# e1-xover.net
KiCad netlist of a schematic drawn in EAGLE
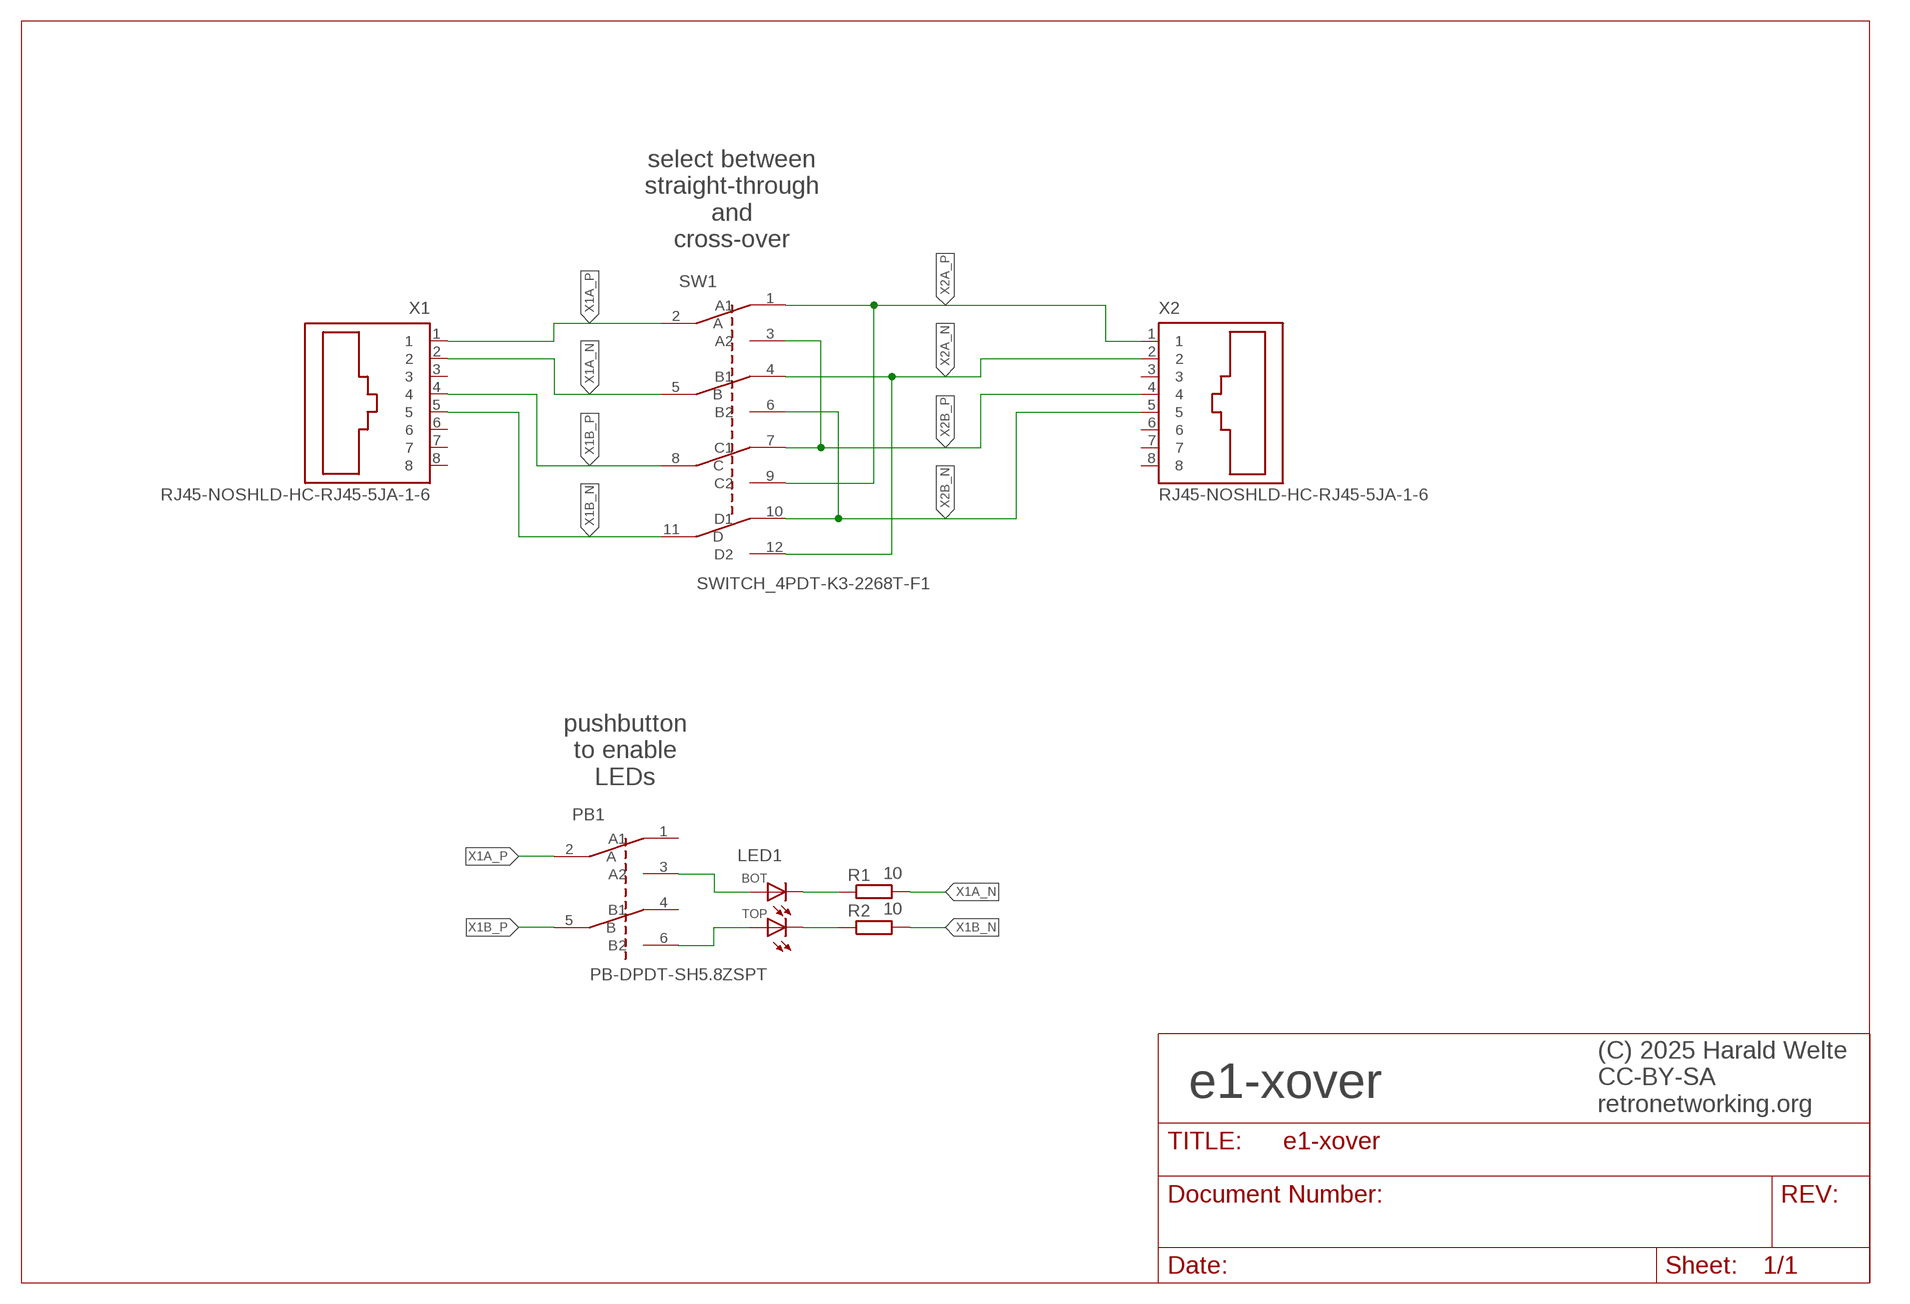
[diagram p0: schematic, sheet 1]

(export (version "E")
  (design (tool "Eeschema 10.0.6"))
  (components
    (comp (ref "LED1")
      (value "DIALIGHT_2V-MHK2512RGTD")
      (footprint "eagle-import:MHK2512RGTD")
      (libsource (lib "eagle-import") (part "DIALIGHT_2V-MHK2512RGTD"))
    )
    (comp (ref "PB1")
      (value "PB-DPDT-SH5.8ZSPT")
      (footprint "eagle-import:SH-5.8ZSPT")
      (libsource (lib "eagle-import") (part "PB-DPDT-SH5.8ZSPT"))
    )
    (comp (ref "R1")
      (value "10")
      (footprint "eagle-import:0207_7")
      (libsource (lib "eagle-import") (part "R-EU_0207/7"))
    )
    (comp (ref "R2")
      (value "10")
      (footprint "eagle-import:0207_7")
      (libsource (lib "eagle-import") (part "R-EU_0207/7"))
    )
    (comp (ref "SW1")
      (value "SWITCH_4PDT-K3-2268T-F1")
      (footprint "eagle-import:K3--2268T-F1")
      (libsource (lib "eagle-import") (part "SWITCH_4PDT-K3-2268T-F1"))
    )
    (comp (ref "X1")
      (value "RJ45-NOSHLD-HC-RJ45-5JA-1-6")
      (footprint "eagle-import:HC-RJ45-5JA-1-6")
      (libsource (lib "eagle-import") (part "RJ45-NOSHLD-HC-RJ45-5JA-1-6"))
    )
    (comp (ref "X2")
      (value "RJ45-NOSHLD-HC-RJ45-5JA-1-6")
      (footprint "eagle-import:HC-RJ45-5JA-1-6")
      (libsource (lib "eagle-import") (part "RJ45-NOSHLD-HC-RJ45-5JA-1-6"))
    )
  )
  (nets
    (net (code "1") (name "Net-(LED1-AB)") (class "Default")
      (node (ref "LED1") (pin "BA") (pinfunction "AB_BA") (pintype "passive"))
      (node (ref "PB1") (pin "3") (pinfunction "A2_3") (pintype "bidirectional"))
    )
    (net (code "2") (name "Net-(LED1-AT)") (class "Default")
      (node (ref "LED1") (pin "AA") (pinfunction "AT_AA") (pintype "passive"))
      (node (ref "PB1") (pin "6") (pinfunction "B2_6") (pintype "bidirectional"))
    )
    (net (code "3") (name "Net-(LED1-CB)") (class "Default")
      (node (ref "LED1") (pin "BK") (pinfunction "CB_BK") (pintype "passive"))
      (node (ref "R1") (pin "1") (pinfunction "1_1") (pintype "passive"))
    )
    (net (code "4") (name "Net-(LED1-CT)") (class "Default")
      (node (ref "LED1") (pin "AK") (pinfunction "CT_AK") (pintype "passive"))
      (node (ref "R2") (pin "1") (pinfunction "1_1") (pintype "passive"))
    )
    (net (code "5") (name "X1A_N") (class "Default")
      (node (ref "R1") (pin "2") (pinfunction "2_2") (pintype "passive"))
      (node (ref "SW1") (pin "5") (pinfunction "B_5") (pintype "bidirectional"))
      (node (ref "X1") (pin "2") (pinfunction "2_2") (pintype "passive"))
    )
    (net (code "6") (name "X1A_P") (class "Default")
      (node (ref "PB1") (pin "2") (pinfunction "A_2") (pintype "bidirectional"))
      (node (ref "SW1") (pin "2") (pinfunction "A_2") (pintype "bidirectional"))
      (node (ref "X1") (pin "1") (pinfunction "1_1") (pintype "passive"))
    )
    (net (code "7") (name "X1B_N") (class "Default")
      (node (ref "R2") (pin "2") (pinfunction "2_2") (pintype "passive"))
      (node (ref "SW1") (pin "11") (pinfunction "D_11") (pintype "bidirectional"))
      (node (ref "X1") (pin "5") (pinfunction "5_5") (pintype "passive"))
    )
    (net (code "8") (name "X1B_P") (class "Default")
      (node (ref "PB1") (pin "5") (pinfunction "B_5") (pintype "bidirectional"))
      (node (ref "SW1") (pin "8") (pinfunction "C_8") (pintype "bidirectional"))
      (node (ref "X1") (pin "4") (pinfunction "4_4") (pintype "passive"))
    )
    (net (code "9") (name "X2A_N") (class "Default")
      (node (ref "SW1") (pin "12") (pinfunction "D2_12") (pintype "bidirectional"))
      (node (ref "SW1") (pin "4") (pinfunction "B1_4") (pintype "bidirectional"))
      (node (ref "X2") (pin "2") (pinfunction "2_2") (pintype "passive"))
    )
    (net (code "10") (name "X2A_P") (class "Default")
      (node (ref "SW1") (pin "1") (pinfunction "A1_1") (pintype "bidirectional"))
      (node (ref "SW1") (pin "9") (pinfunction "C2_9") (pintype "bidirectional"))
      (node (ref "X2") (pin "1") (pinfunction "1_1") (pintype "passive"))
    )
    (net (code "11") (name "X2B_N") (class "Default")
      (node (ref "SW1") (pin "10") (pinfunction "D1_10") (pintype "bidirectional"))
      (node (ref "SW1") (pin "6") (pinfunction "B2_6") (pintype "bidirectional"))
      (node (ref "X2") (pin "5") (pinfunction "5_5") (pintype "passive"))
    )
    (net (code "12") (name "X2B_P") (class "Default")
      (node (ref "SW1") (pin "3") (pinfunction "A2_3") (pintype "bidirectional"))
      (node (ref "SW1") (pin "7") (pinfunction "C1_7") (pintype "bidirectional"))
      (node (ref "X2") (pin "4") (pinfunction "4_4") (pintype "passive"))
    )
    (net (code "13") (name "unconnected-(PB1-A1-Pad1)") (class "Default")
      (node (ref "PB1") (pin "1") (pinfunction "A1_1") (pintype "bidirectional"))
    )
    (net (code "14") (name "unconnected-(PB1-B1-Pad4)") (class "Default")
      (node (ref "PB1") (pin "4") (pinfunction "B1_4") (pintype "bidirectional"))
    )
    (net (code "15") (name "unconnected-(X1-Pad3)") (class "Default")
      (node (ref "X1") (pin "3") (pinfunction "3_3") (pintype "passive"))
    )
    (net (code "16") (name "unconnected-(X1-Pad6)") (class "Default")
      (node (ref "X1") (pin "6") (pinfunction "6_6") (pintype "passive"))
    )
    (net (code "17") (name "unconnected-(X1-Pad7)") (class "Default")
      (node (ref "X1") (pin "7") (pinfunction "7_7") (pintype "passive"))
    )
    (net (code "18") (name "unconnected-(X1-Pad8)") (class "Default")
      (node (ref "X1") (pin "8") (pinfunction "8_8") (pintype "passive"))
    )
    (net (code "19") (name "unconnected-(X2-Pad3)") (class "Default")
      (node (ref "X2") (pin "3") (pinfunction "3_3") (pintype "passive"))
    )
    (net (code "20") (name "unconnected-(X2-Pad6)") (class "Default")
      (node (ref "X2") (pin "6") (pinfunction "6_6") (pintype "passive"))
    )
    (net (code "21") (name "unconnected-(X2-Pad7)") (class "Default")
      (node (ref "X2") (pin "7") (pinfunction "7_7") (pintype "passive"))
    )
    (net (code "22") (name "unconnected-(X2-Pad8)") (class "Default")
      (node (ref "X2") (pin "8") (pinfunction "8_8") (pintype "passive"))
    )
  )
)
